# motordriver.net
KiCad netlist of a schematic drawn in EAGLE
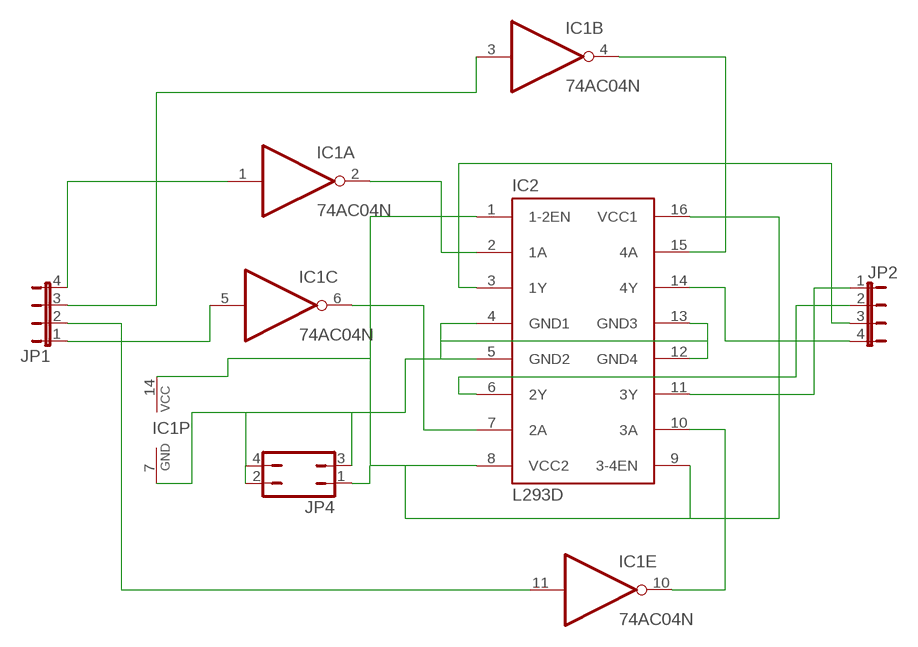
[diagram p0: schematic, sheet 1]

(export (version "E")
  (design (tool "Eeschema 10.0.6"))
  (components
    (comp (ref "IC1")
      (value "74AC04N")
      (footprint "eagle-import:DIL14")
      (libsource (lib "eagle-import") (part "7404NAC"))
    )
    (comp (ref "IC2")
      (value "L293D")
      (footprint "eagle-import:DIL16")
      (libsource (lib "eagle-import") (part "L293D"))
    )
    (comp (ref "JP1")
      (value "JP4E")
      (footprint "eagle-import:JP4")
      (libsource (lib "eagle-import") (part "JP4E"))
    )
    (comp (ref "JP2")
      (value "JP4E")
      (footprint "eagle-import:JP4")
      (libsource (lib "eagle-import") (part "JP4E"))
    )
    (comp (ref "JP4")
      (value "JP2Q")
      (footprint "eagle-import:JP2Q")
      (libsource (lib "eagle-import") (part "JP2Q"))
    )
  )
  (nets
    (net (code "1") (name "Net-(IC1A-I)") (class "Default")
      (node (ref "IC1") (pin "1") (pinfunction "I_1") (pintype "input"))
      (node (ref "JP1") (pin "4") (pinfunction "4_4") (pintype "passive"))
    )
    (net (code "2") (name "Net-(IC1A-O)") (class "Default")
      (node (ref "IC1") (pin "2") (pinfunction "O_2") (pintype "output"))
      (node (ref "IC2") (pin "2") (pinfunction "1A_2") (pintype "input"))
    )
    (net (code "3") (name "Net-(IC1B-I)") (class "Default")
      (node (ref "IC1") (pin "3") (pinfunction "I_3") (pintype "input"))
      (node (ref "JP1") (pin "3") (pinfunction "3_3") (pintype "passive"))
    )
    (net (code "4") (name "Net-(IC1B-O)") (class "Default")
      (node (ref "IC1") (pin "4") (pinfunction "O_4") (pintype "output"))
      (node (ref "IC2") (pin "15") (pinfunction "4A_15") (pintype "input"))
    )
    (net (code "5") (name "Net-(IC1C-I)") (class "Default")
      (node (ref "IC1") (pin "5") (pinfunction "I_5") (pintype "input"))
      (node (ref "JP1") (pin "1") (pinfunction "1_1") (pintype "passive"))
    )
    (net (code "6") (name "Net-(IC1C-O)") (class "Default")
      (node (ref "IC1") (pin "6") (pinfunction "O_6") (pintype "output"))
      (node (ref "IC2") (pin "7") (pinfunction "2A_7") (pintype "input"))
    )
    (net (code "7") (name "Net-(IC1E-I)") (class "Default")
      (node (ref "IC1") (pin "11") (pinfunction "I_11") (pintype "input"))
      (node (ref "JP1") (pin "2") (pinfunction "2_2") (pintype "passive"))
    )
    (net (code "8") (name "Net-(IC1E-O)") (class "Default")
      (node (ref "IC1") (pin "10") (pinfunction "O_10") (pintype "output"))
      (node (ref "IC2") (pin "10") (pinfunction "3A_10") (pintype "input"))
    )
    (net (code "9") (name "Net-(IC1G-GND)") (class "Default")
      (node (ref "IC1") (pin "7") (pinfunction "GND_7") (pintype "power_in"))
      (node (ref "IC2") (pin "12") (pinfunction "GND4_12") (pintype "power_in"))
      (node (ref "IC2") (pin "13") (pinfunction "GND3_13") (pintype "power_in"))
      (node (ref "IC2") (pin "4") (pinfunction "GND1_4") (pintype "power_in"))
      (node (ref "IC2") (pin "5") (pinfunction "GND2_5") (pintype "power_in"))
      (node (ref "JP4") (pin "2") (pinfunction "2_2") (pintype "passive"))
      (node (ref "JP4") (pin "3") (pinfunction "3_3") (pintype "passive"))
      (node (ref "JP4") (pin "4") (pinfunction "4_4") (pintype "passive"))
    )
    (net (code "10") (name "Net-(IC1G-VCC)") (class "Default")
      (node (ref "IC1") (pin "14") (pinfunction "VCC_14") (pintype "power_in"))
      (node (ref "IC2") (pin "1") (pinfunction "1-2EN_1") (pintype "input"))
      (node (ref "IC2") (pin "16") (pinfunction "VCC1_16") (pintype "power_in"))
      (node (ref "IC2") (pin "8") (pinfunction "VCC2_8") (pintype "power_in"))
      (node (ref "IC2") (pin "9") (pinfunction "3-4EN_9") (pintype "input"))
      (node (ref "JP4") (pin "1") (pinfunction "1_1") (pintype "passive"))
    )
    (net (code "11") (name "Net-(IC2-1Y)") (class "Default")
      (node (ref "IC2") (pin "3") (pinfunction "1Y_3") (pintype "output"))
      (node (ref "JP2") (pin "3") (pinfunction "3_3") (pintype "passive"))
    )
    (net (code "12") (name "Net-(IC2-2Y)") (class "Default")
      (node (ref "IC2") (pin "6") (pinfunction "2Y_6") (pintype "output"))
      (node (ref "JP2") (pin "2") (pinfunction "2_2") (pintype "passive"))
    )
    (net (code "13") (name "Net-(IC2-3Y)") (class "Default")
      (node (ref "IC2") (pin "11") (pinfunction "3Y_11") (pintype "output"))
      (node (ref "JP2") (pin "1") (pinfunction "1_1") (pintype "passive"))
    )
    (net (code "14") (name "Net-(IC2-4Y)") (class "Default")
      (node (ref "IC2") (pin "14") (pinfunction "4Y_14") (pintype "output"))
      (node (ref "JP2") (pin "4") (pinfunction "4_4") (pintype "passive"))
    )
  )
)
